# MC21R01_Inverter_1.net
KiCad netlist of a schematic drawn in Altium Designer
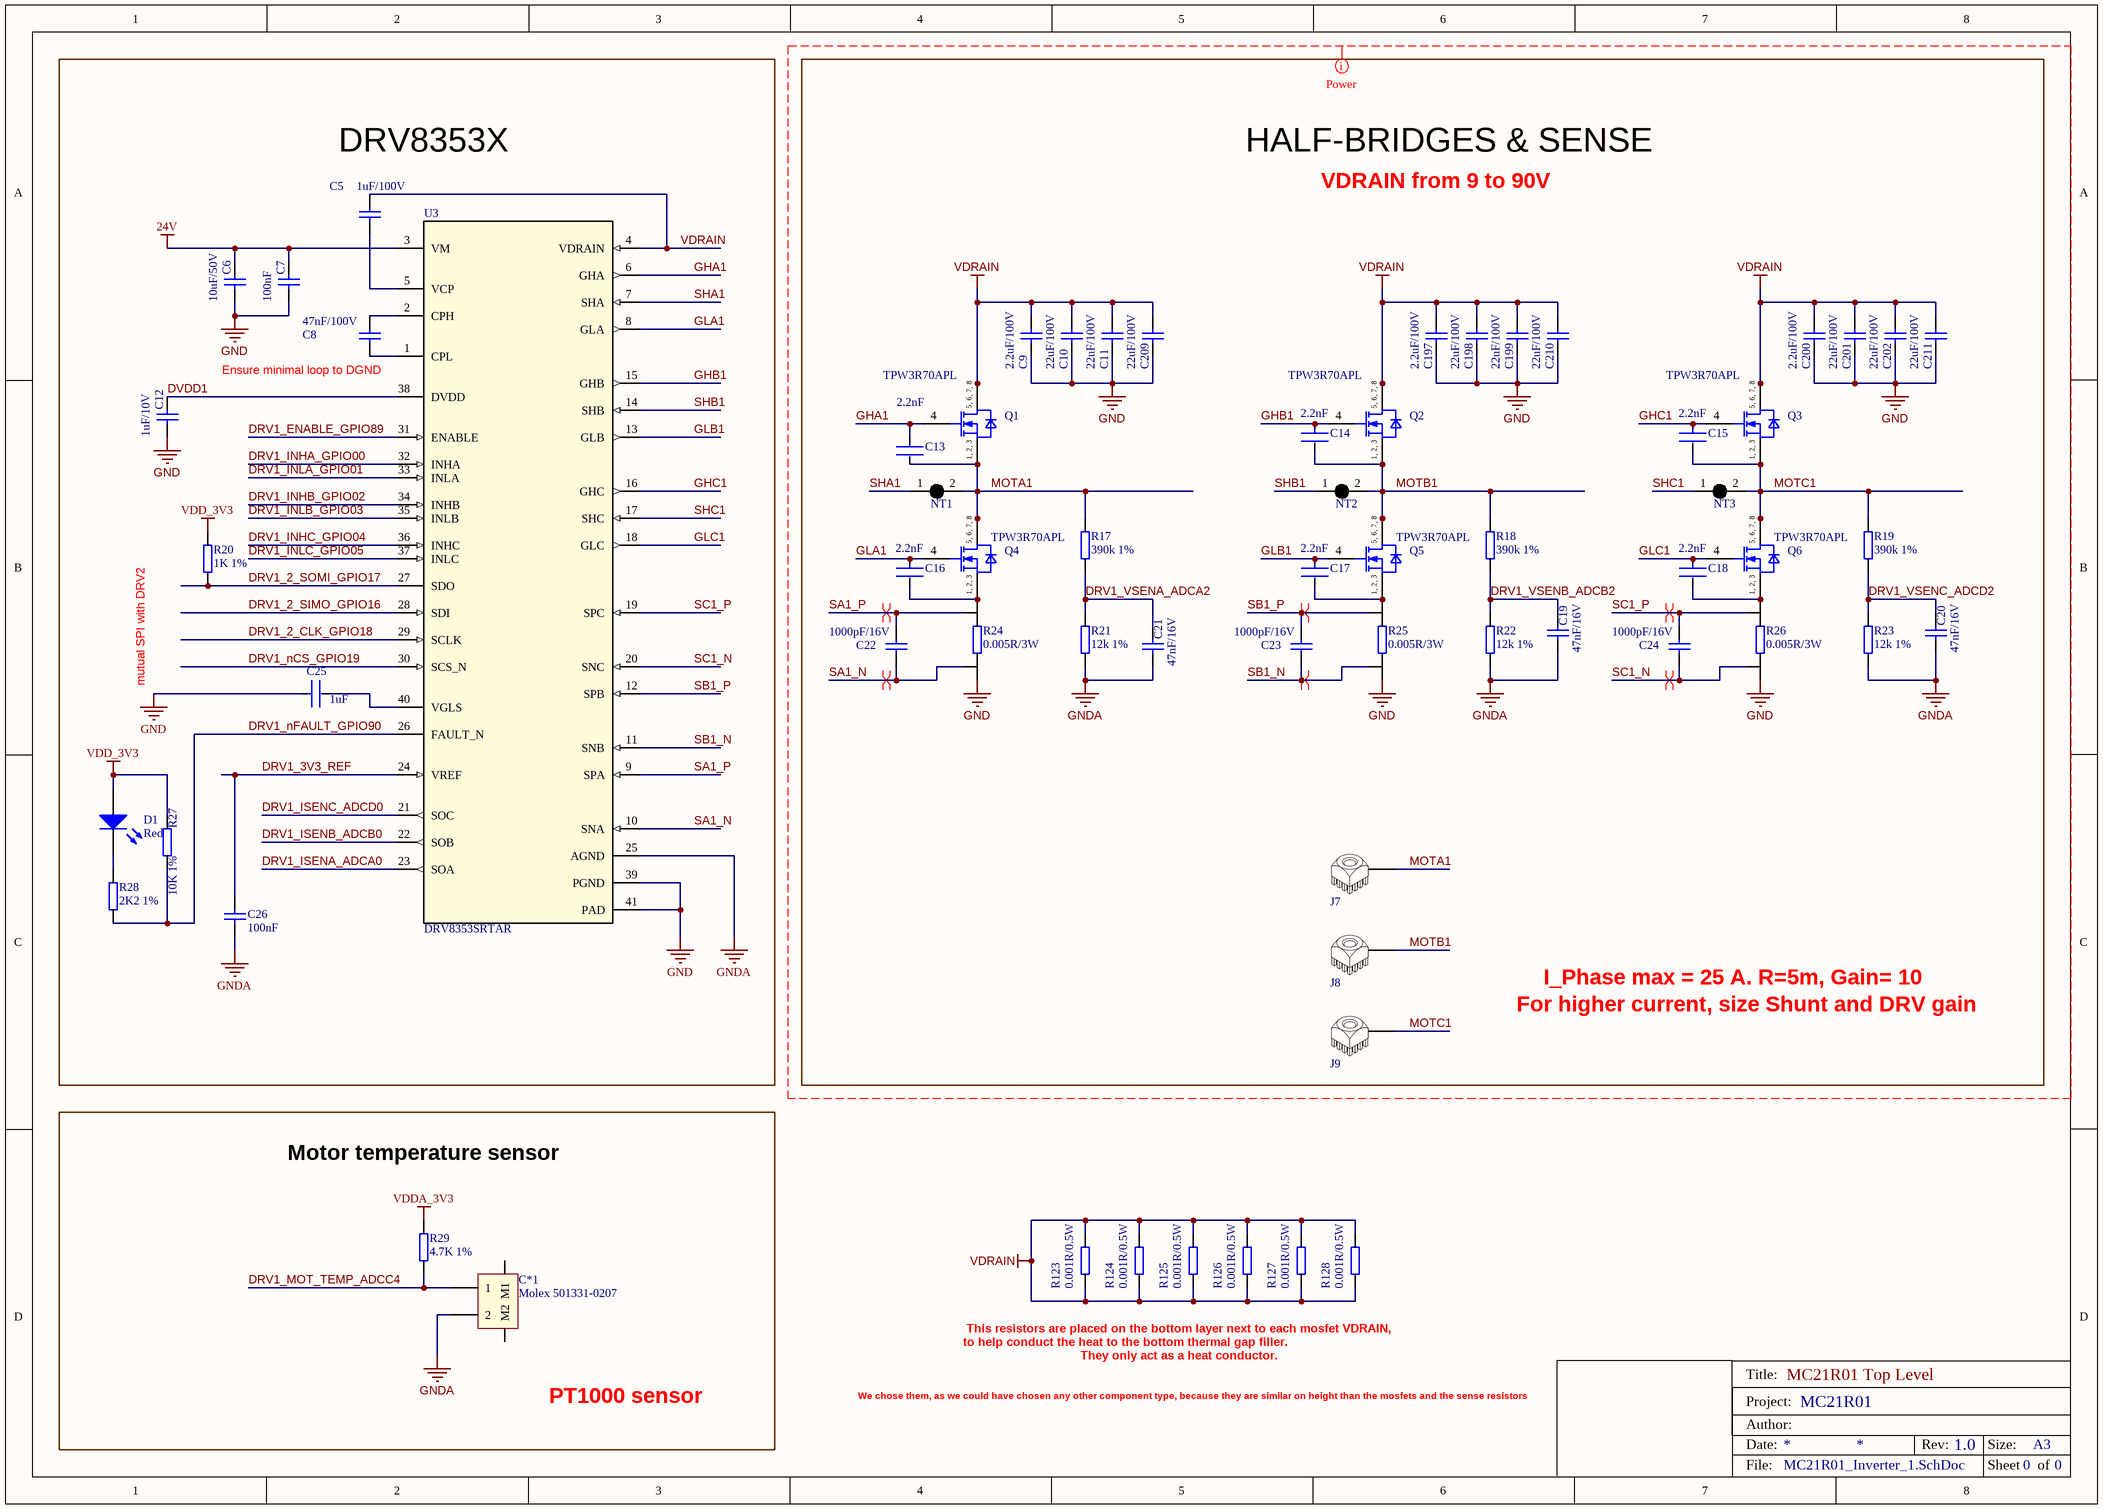
[diagram p0: MC21R01_Inverter_1.SchDoc]

(export (version "E")
  (design (tool "Eeschema 10.0.6"))
  (components
    (comp (ref "C*1")
      (value "Molex 501331-0207")
      (footprint "Molex 501331-0207")
      (description "PicoClasp 02 pin vertical")
      (libsource (lib "PAL_Molex") (part "Molex 501331-0207"))
    )
    (comp (ref "C5")
      (value "1uF/100V")
      (footprint "PAL_Capacitors:0805 SMD capacitor")
      (description "1 uF 100 V 0805  ±10% Tolerance X7R Multilayer Ceramic Chip Capacitor")
      (fields (field (name "Comment") "1uF/100V 0805 10% X7R"))
      (libsource (lib "PAL_Capacitors") (part "1uF/100V 0805 10% X7R"))
    )
    (comp (ref "C6")
      (value "10uF/50V")
      (footprint "PAL_Capacitors:1206 SMD Capacitor")
      (description "10 uF 50 V 1206 ±20% Tolerance X5R Multilayer Ceramic Chip Capacitor")
      (fields (field (name "Comment") "10uf/50V 1206 20% X5R"))
      (libsource (lib "PAL_Capacitors") (part "10uF/50V 1206 20% X5R"))
    )
    (comp (ref "C7")
      (value "100nF")
      (footprint "CAPC0603X03N")
      (description "100nF/25V 0201 10% Tolerance X6S Multilayer Ceramic Chip Capacitor")
      (fields (field (name "TOLERANCE") "10%") (field (name "Comment") "100nF/25V 0201 10% X6S"))
      (libsource (lib "Wandercraft") (part "STD_CAP_2PIN_NPOL"))
    )
    (comp (ref "C8")
      (value "47nF/100V")
      (footprint "PAL_Capacitors:0603 SMD capacitor")
      (description "47 nF 100 V 0603 ±10% Tolerance X7R Multilayer Ceramic Chip Capacitor")
      (fields (field (name "Comment") "47nF/100V 0603 10% X7R"))
      (libsource (lib "PAL_Capacitors") (part "47nF/100V 0603 10% X7R_1"))
    )
    (comp (ref "C9")
      (value "2.2uF/100V")
      (footprint "1210 SMD capacitor h=2mm")
      (description "2.2 uF 100 V 1210  ±10% Tolerance X7R Multilayer Ceramic Chip Capacitor")
      (fields (field (name "Comment") "2.2uF/100V 1210 10% X7R"))
      (libsource (lib "PAL_Capacitors") (part "2.2uF/100V 1210 10% X7R"))
    )
    (comp (ref "C10")
      (value "22uF/100V")
      (footprint "PAL_Capacitors:2220 SMD Capacitor H=5MM")
      (description "22 uF 100 V 2220 ±20% Tolerance X7S Multilayer Ceramic Chip Capacitor")
      (fields (field (name "Comment") "22uF/100V 2220 20% X7S"))
      (libsource (lib "PAL_Capacitors") (part "22uF/100V 2220 20% X7S"))
    )
    (comp (ref "C11")
      (value "22uF/100V")
      (footprint "PAL_Capacitors:2220 SMD Capacitor H=5MM")
      (description "22 uF 100 V 2220 ±20% Tolerance X7S Multilayer Ceramic Chip Capacitor")
      (fields (field (name "Comment") "22uF/100V 2220 20% X7S"))
      (libsource (lib "PAL_Capacitors") (part "22uF/100V 2220 20% X7S"))
    )
    (comp (ref "C12")
      (value "1uF/10V")
      (footprint "PAL_Capacitors:0603 SMD capacitor")
      (description "1uF/10V 0603 10% Tolerance X7R Multilayer Ceramic Chip Capacitor")
      (fields (field (name "Comment") "1uF/10V 0603 10% X7R"))
      (libsource (lib "PAL_Capacitors") (part "1uF/10V 0603 10% X7R"))
    )
    (comp (ref "C13")
      (value "2200pF/50V 0201 10% X7R")
      (footprint "FP-GRM033-0_03-IPC_A")
      (description "2200pF/50V 0201 10% Tolerance X7R Multilayer Ceramic Chip Capacitor")
      (fields (field (name "TOLERANCE") "10%") (field (name "CAPACITANCE") "2.2nF"))
      (libsource (lib "Altium Content Vault") (part "b4654b650e69147ec39a6b967a45e02"))
    )
    (comp (ref "C14")
      (value "2200pF/50V 0201 10% X7R")
      (footprint "FP-GRM033-0_03-IPC_A")
      (description "2200pF/50V 0201 10% Tolerance X7R Multilayer Ceramic Chip Capacitor")
      (fields (field (name "TOLERANCE") "10%") (field (name "CAPACITANCE") "2.2nF"))
      (libsource (lib "Altium Content Vault") (part "b4654b650e69147ec39a6b967a45e02"))
    )
    (comp (ref "C15")
      (value "2200pF/50V 0201 10% X7R")
      (footprint "FP-GRM033-0_03-IPC_A")
      (description "2200pF/50V 0201 10% Tolerance X7R Multilayer Ceramic Chip Capacitor")
      (fields (field (name "TOLERANCE") "10%") (field (name "CAPACITANCE") "2.2nF"))
      (libsource (lib "Altium Content Vault") (part "b4654b650e69147ec39a6b967a45e02"))
    )
    (comp (ref "C16")
      (value "2200pF/50V 0201 10% X7R")
      (footprint "FP-GRM033-0_03-IPC_A")
      (description "2200pF/50V 0201 10% Tolerance X7R Multilayer Ceramic Chip Capacitor")
      (fields (field (name "TOLERANCE") "10%") (field (name "CAPACITANCE") "2.2nF"))
      (libsource (lib "Altium Content Vault") (part "b4654b650e69147ec39a6b967a45e02"))
    )
    (comp (ref "C17")
      (value "2200pF/50V 0201 10% X7R")
      (footprint "FP-GRM033-0_03-IPC_A")
      (description "2200pF/50V 0201 10% Tolerance X7R Multilayer Ceramic Chip Capacitor")
      (fields (field (name "TOLERANCE") "10%") (field (name "CAPACITANCE") "2.2nF"))
      (libsource (lib "Altium Content Vault") (part "b4654b650e69147ec39a6b967a45e02"))
    )
    (comp (ref "C18")
      (value "2200pF/50V 0201 10% X7R")
      (footprint "FP-GRM033-0_03-IPC_A")
      (description "2200pF/50V 0201 10% Tolerance X7R Multilayer Ceramic Chip Capacitor")
      (fields (field (name "TOLERANCE") "10%") (field (name "CAPACITANCE") "2.2nF"))
      (libsource (lib "Altium Content Vault") (part "b4654b650e69147ec39a6b967a45e02"))
    )
    (comp (ref "C19")
      (value "47nF/16V")
      (footprint "PAL_Capacitors:0402 SMD Capacitor")
      (description "47nF/16V 0402 10% Tolerance X7R Multilayer Ceramic Chip Capacitor")
      (fields (field (name "Comment") "47nF/16V 0402 10% X7R"))
      (libsource (lib "PAL_Capacitors") (part "47nF/16V 0402 10% X7R"))
    )
    (comp (ref "C20")
      (value "47nF/16V")
      (footprint "PAL_Capacitors:0402 SMD Capacitor")
      (description "47nF/16V 0402 10% Tolerance X7R Multilayer Ceramic Chip Capacitor")
      (fields (field (name "Comment") "47nF/16V 0402 10% X7R"))
      (libsource (lib "PAL_Capacitors") (part "47nF/16V 0402 10% X7R"))
    )
    (comp (ref "C21")
      (value "47nF/16V")
      (footprint "PAL_Capacitors:0402 SMD Capacitor")
      (description "47nF/16V 0402 10% Tolerance X7R Multilayer Ceramic Chip Capacitor")
      (fields (field (name "Comment") "47nF/16V 0402 10% X7R"))
      (libsource (lib "PAL_Capacitors") (part "47nF/16V 0402 10% X7R"))
    )
    (comp (ref "C22")
      (value "1000pF/16V")
      (footprint "PAL_Capacitors:0402 SMD Capacitor")
      (description "1000pF/16V 0402 10% Tolerance X7R Multilayer Ceramic Chip Capacitor")
      (fields (field (name "Comment") "1000pF/16V 0402 10% X7R"))
      (libsource (lib "PAL_Capacitors") (part "1000pF/16V 0402 10% X7R_1"))
    )
    (comp (ref "C23")
      (value "1000pF/16V")
      (footprint "PAL_Capacitors:0402 SMD Capacitor")
      (description "1000pF/16V 0402 10% Tolerance X7R Multilayer Ceramic Chip Capacitor")
      (fields (field (name "Comment") "1000pF/16V 0402 10% X7R"))
      (libsource (lib "PAL_Capacitors") (part "1000pF/16V 0402 10% X7R_1"))
    )
    (comp (ref "C24")
      (value "1000pF/16V")
      (footprint "PAL_Capacitors:0402 SMD Capacitor")
      (description "1000pF/16V 0402 10% Tolerance X7R Multilayer Ceramic Chip Capacitor")
      (fields (field (name "Comment") "1000pF/16V 0402 10% X7R"))
      (libsource (lib "PAL_Capacitors") (part "1000pF/16V 0402 10% X7R_1"))
    )
    (comp (ref "C25")
      (value "1uF/6.3V 0201 10% X5R")
      (footprint "FP-CL03-IPC_A")
      (description "1uF/6.3V 0201 10% Tolerance X5R Multilayer Ceramic Chip Capacitor")
      (fields (field (name "TOLERANCE") "20%") (field (name "CAPACITANCE") "1uF"))
      (libsource (lib "Altium Content Vault") (part "b4654b650e69147ec39a6b967a45e02"))
    )
    (comp (ref "C26")
      (value "100nF")
      (footprint "CAPC0603X03N")
      (description "100nF/25V 0201 10% Tolerance X6S Multilayer Ceramic Chip Capacitor")
      (fields (field (name "TOLERANCE") "10%") (field (name "Comment") "100nF/25V 0201 10% X6S"))
      (libsource (lib "Wandercraft") (part "STD_CAP_2PIN_NPOL"))
    )
    (comp (ref "C197")
      (value "2.2uF/100V")
      (footprint "1210 SMD capacitor h=2mm")
      (description "2.2 uF 100 V 1210  ±10% Tolerance X7R Multilayer Ceramic Chip Capacitor")
      (fields (field (name "Comment") "2.2uF/100V 1210 10% X7R"))
      (libsource (lib "PAL_Capacitors") (part "2.2uF/100V 1210 10% X7R"))
    )
    (comp (ref "C198")
      (value "22uF/100V")
      (footprint "PAL_Capacitors:2220 SMD Capacitor H=5MM")
      (description "22 uF 100 V 2220 ±20% Tolerance X7S Multilayer Ceramic Chip Capacitor")
      (fields (field (name "Comment") "22uF/100V 2220 20% X7S"))
      (libsource (lib "PAL_Capacitors") (part "22uF/100V 2220 20% X7S"))
    )
    (comp (ref "C199")
      (value "22uF/100V")
      (footprint "PAL_Capacitors:2220 SMD Capacitor H=5MM")
      (description "22 uF 100 V 2220 ±20% Tolerance X7S Multilayer Ceramic Chip Capacitor")
      (fields (field (name "Comment") "22uF/100V 2220 20% X7S"))
      (libsource (lib "PAL_Capacitors") (part "22uF/100V 2220 20% X7S"))
    )
    (comp (ref "C200")
      (value "2.2uF/100V")
      (footprint "1210 SMD capacitor h=2mm")
      (description "2.2 uF 100 V 1210  ±10% Tolerance X7R Multilayer Ceramic Chip Capacitor")
      (fields (field (name "Comment") "2.2uF/100V 1210 10% X7R"))
      (libsource (lib "PAL_Capacitors") (part "2.2uF/100V 1210 10% X7R"))
    )
    (comp (ref "C201")
      (value "22uF/100V")
      (footprint "PAL_Capacitors:2220 SMD Capacitor H=5MM")
      (description "22 uF 100 V 2220 ±20% Tolerance X7S Multilayer Ceramic Chip Capacitor")
      (fields (field (name "Comment") "22uF/100V 2220 20% X7S"))
      (libsource (lib "PAL_Capacitors") (part "22uF/100V 2220 20% X7S"))
    )
    (comp (ref "C202")
      (value "22uF/100V")
      (footprint "PAL_Capacitors:2220 SMD Capacitor H=5MM")
      (description "22 uF 100 V 2220 ±20% Tolerance X7S Multilayer Ceramic Chip Capacitor")
      (fields (field (name "Comment") "22uF/100V 2220 20% X7S"))
      (libsource (lib "PAL_Capacitors") (part "22uF/100V 2220 20% X7S"))
    )
    (comp (ref "C209")
      (value "22uF/100V")
      (footprint "PAL_Capacitors:2220 SMD Capacitor H=5MM")
      (description "22 uF 100 V 2220 ±20% Tolerance X7S Multilayer Ceramic Chip Capacitor")
      (fields (field (name "Comment") "22uF/100V 2220 20% X7S"))
      (libsource (lib "PAL_Capacitors") (part "22uF/100V 2220 20% X7S"))
    )
    (comp (ref "C210")
      (value "22uF/100V")
      (footprint "PAL_Capacitors:2220 SMD Capacitor H=5MM")
      (description "22 uF 100 V 2220 ±20% Tolerance X7S Multilayer Ceramic Chip Capacitor")
      (fields (field (name "Comment") "22uF/100V 2220 20% X7S"))
      (libsource (lib "PAL_Capacitors") (part "22uF/100V 2220 20% X7S"))
    )
    (comp (ref "C211")
      (value "22uF/100V")
      (footprint "PAL_Capacitors:2220 SMD Capacitor H=5MM")
      (description "22 uF 100 V 2220 ±20% Tolerance X7S Multilayer Ceramic Chip Capacitor")
      (fields (field (name "Comment") "22uF/100V 2220 20% X7S"))
      (libsource (lib "PAL_Capacitors") (part "22uF/100V 2220 20% X7S"))
    )
    (comp (ref "D1")
      (value "Red")
      (footprint "0402 SMD LED Red")
      (description "Low Profile Chip LED, Red")
      (fields (field (name "MANUFACTURER") "ROHM") (field (name "MANUFACTURER PART NUMBER") "SML-P11UTT86R"))
      (libsource (lib "PAL_devices") (part "LED_0402_Red"))
    )
    (comp (ref "J7")
      (value "WE_7461094")
      (footprint "WE_7461094")
      (description "REDCUBE PRESS-FIT with external thread and full plain pin-plate WPSHFU, 130A, M3 screw, 9pins")
      (fields
        (field (name "MANUFACTURER") "WURTH ELEKTRONIK")
        (field (name "MANUFACTURER PART NUMBER") "7461094")
        (field (name "CREATED BY") "Yaiza Montes")
      )
      (libsource (lib "PAL_Wurth_2020") (part "WE_7461094"))
    )
    (comp (ref "J8")
      (value "WE_7461094")
      (footprint "WE_7461094")
      (description "REDCUBE PRESS-FIT with external thread and full plain pin-plate WPSHFU, 130A, M3 screw, 9pins")
      (fields
        (field (name "MANUFACTURER") "WURTH ELEKTRONIK")
        (field (name "MANUFACTURER PART NUMBER") "7461094")
        (field (name "CREATED BY") "Yaiza Montes")
      )
      (libsource (lib "PAL_Wurth_2020") (part "WE_7461094"))
    )
    (comp (ref "J9")
      (value "WE_7461094")
      (footprint "WE_7461094")
      (description "REDCUBE PRESS-FIT with external thread and full plain pin-plate WPSHFU, 130A, M3 screw, 9pins")
      (fields
        (field (name "MANUFACTURER") "WURTH ELEKTRONIK")
        (field (name "MANUFACTURER PART NUMBER") "7461094")
        (field (name "CREATED BY") "Yaiza Montes")
      )
      (libsource (lib "PAL_Wurth_2020") (part "WE_7461094"))
    )
    (comp (ref "NT1")
      (value "Net Tie SMD")
      (footprint "PAL_devices:Net Tie SMD 0.4x0.8mm")
      (description "Net Tie starpoint")
      (libsource (lib "PAL_devices") (part "Net Tie SMD"))
    )
    (comp (ref "NT2")
      (value "Net Tie SMD")
      (footprint "PAL_devices:Net Tie SMD 0.4x0.8mm")
      (description "Net Tie starpoint")
      (libsource (lib "PAL_devices") (part "Net Tie SMD"))
    )
    (comp (ref "NT3")
      (value "Net Tie SMD")
      (footprint "PAL_devices:Net Tie SMD 0.4x0.8mm")
      (description "Net Tie starpoint")
      (libsource (lib "PAL_devices") (part "Net Tie SMD"))
    )
    (comp (ref "Q1")
      (value "TPW3R70APL")
      (footprint "DSOP Advance Toshiba")
      (description "Silicon N-channel MOS (U-MOS-H)")
      (fields (field (name "MANUFACTURER") "Toshiba Semicon"))
      (libsource (lib "PAL_devices") (part "TPW3R70APL"))
    )
    (comp (ref "Q2")
      (value "TPW3R70APL")
      (footprint "DSOP Advance Toshiba")
      (description "Silicon N-channel MOS (U-MOS-H)")
      (fields (field (name "MANUFACTURER") "Toshiba Semicon"))
      (libsource (lib "PAL_devices") (part "TPW3R70APL"))
    )
    (comp (ref "Q3")
      (value "TPW3R70APL")
      (footprint "DSOP Advance Toshiba")
      (description "Silicon N-channel MOS (U-MOS-H)")
      (fields (field (name "MANUFACTURER") "Toshiba Semicon"))
      (libsource (lib "PAL_devices") (part "TPW3R70APL"))
    )
    (comp (ref "Q4")
      (value "TPW3R70APL")
      (footprint "DSOP Advance Toshiba")
      (description "Silicon N-channel MOS (U-MOS-H)")
      (fields (field (name "MANUFACTURER") "Toshiba Semicon"))
      (libsource (lib "PAL_devices") (part "TPW3R70APL"))
    )
    (comp (ref "Q5")
      (value "TPW3R70APL")
      (footprint "DSOP Advance Toshiba")
      (description "Silicon N-channel MOS (U-MOS-H)")
      (fields (field (name "MANUFACTURER") "Toshiba Semicon"))
      (libsource (lib "PAL_devices") (part "TPW3R70APL"))
    )
    (comp (ref "Q6")
      (value "TPW3R70APL")
      (footprint "DSOP Advance Toshiba")
      (description "Silicon N-channel MOS (U-MOS-H)")
      (fields (field (name "MANUFACTURER") "Toshiba Semicon"))
      (libsource (lib "PAL_devices") (part "TPW3R70APL"))
    )
    (comp (ref "R17")
      (value "390k 1%")
      (footprint "PAL_Resistors:0603 SMD resistor")
      (description "390k/150V 1% 0603 250mW SMD Resistor")
      (libsource (lib "PAL_Resistors") (part "390k/150V 1% 0603 250mW"))
    )
    (comp (ref "R18")
      (value "390k 1%")
      (footprint "PAL_Resistors:0603 SMD resistor")
      (description "390k/150V 1% 0603 250mW SMD Resistor")
      (libsource (lib "PAL_Resistors") (part "390k/150V 1% 0603 250mW"))
    )
    (comp (ref "R19")
      (value "390k 1%")
      (footprint "PAL_Resistors:0603 SMD resistor")
      (description "390k/150V 1% 0603 250mW SMD Resistor")
      (libsource (lib "PAL_Resistors") (part "390k/150V 1% 0603 250mW"))
    )
    (comp (ref "R20")
      (value "1K 1%")
      (footprint "0402 SMD rESISTOR")
      (description "1K/50V 1% 0402 100mW SMD Resistor")
      (libsource (lib "PAL_Resistors") (part "1K/50V 1% 0402 100mW"))
    )
    (comp (ref "R21")
      (value "12k 1%")
      (footprint "PAL_Resistors:0603 SMD resistor")
      (description "12k/150V 1% 0603 250mW SMD Resistor")
      (libsource (lib "PAL_Resistors") (part "12k/150V 1% 0603 250mW"))
    )
    (comp (ref "R22")
      (value "12k 1%")
      (footprint "PAL_Resistors:0603 SMD resistor")
      (description "12k/150V 1% 0603 250mW SMD Resistor")
      (libsource (lib "PAL_Resistors") (part "12k/150V 1% 0603 250mW"))
    )
    (comp (ref "R23")
      (value "12k 1%")
      (footprint "PAL_Resistors:0603 SMD resistor")
      (description "12k/150V 1% 0603 250mW SMD Resistor")
      (libsource (lib "PAL_Resistors") (part "12k/150V 1% 0603 250mW"))
    )
    (comp (ref "R24")
      (value "0.005R/3W")
      (footprint "PAL_Resistors:2512 SMD Resistor V2 NETTIE")
      (description "0.005R/3W 1% 2512 shunt SMD Resistor")
      (libsource (lib "PAL_Resistors") (part "0.005R/3W 1% 2512 Shunt"))
    )
    (comp (ref "R25")
      (value "0.005R/3W")
      (footprint "PAL_Resistors:2512 SMD Resistor V2 NETTIE")
      (description "0.005R/3W 1% 2512 shunt SMD Resistor")
      (libsource (lib "PAL_Resistors") (part "0.005R/3W 1% 2512 Shunt"))
    )
    (comp (ref "R26")
      (value "0.005R/3W")
      (footprint "PAL_Resistors:2512 SMD Resistor V2 NETTIE")
      (description "0.005R/3W 1% 2512 shunt SMD Resistor")
      (libsource (lib "PAL_Resistors") (part "0.005R/3W 1% 2512 Shunt"))
    )
    (comp (ref "R27")
      (value "10K 1%")
      (footprint "0402 SMD rESISTOR")
      (description "10K/50V 1% 0402 100mW SMD Resistor")
      (libsource (lib "PAL_Resistors") (part "10K/50V 1% 0402 100mW"))
    )
    (comp (ref "R28")
      (value "2K2 1%")
      (footprint "0402 SMD rESISTOR")
      (description "2K2/50V 1% 0402 100mW SMD Resistor")
      (libsource (lib "PAL_Resistors") (part "2K2/50V 1% 0402 100mW"))
    )
    (comp (ref "R29")
      (value "4.7K 1%")
      (footprint "0402 SMD rESISTOR")
      (description "4.7K/50V 1% 0402 100mW SMD Resistor")
      (libsource (lib "PAL_Resistors") (part "4.7K/50V 1% 0402 100mW"))
    )
    (comp (ref "R123")
      (value "0.001R/0.5W")
      (footprint "PAL_Resistors:2010 SMD Resistor VERTICAL")
      (description "0.001R/0.5W 1% 2010 shunt SMD Resistor")
      (libsource (lib "PAL_Resistors") (part "0.001R/0.5W 1% 2010 Shunt"))
    )
    (comp (ref "R124")
      (value "0.001R/0.5W")
      (footprint "PAL_Resistors:2010 SMD Resistor VERTICAL")
      (description "0.001R/0.5W 1% 2010 shunt SMD Resistor")
      (libsource (lib "PAL_Resistors") (part "0.001R/0.5W 1% 2010 Shunt"))
    )
    (comp (ref "R125")
      (value "0.001R/0.5W")
      (footprint "PAL_Resistors:2010 SMD Resistor VERTICAL")
      (description "0.001R/0.5W 1% 2010 shunt SMD Resistor")
      (libsource (lib "PAL_Resistors") (part "0.001R/0.5W 1% 2010 Shunt"))
    )
    (comp (ref "R126")
      (value "0.001R/0.5W")
      (footprint "PAL_Resistors:2010 SMD Resistor VERTICAL")
      (description "0.001R/0.5W 1% 2010 shunt SMD Resistor")
      (libsource (lib "PAL_Resistors") (part "0.001R/0.5W 1% 2010 Shunt"))
    )
    (comp (ref "R127")
      (value "0.001R/0.5W")
      (footprint "PAL_Resistors:2010 SMD Resistor VERTICAL")
      (description "0.001R/0.5W 1% 2010 shunt SMD Resistor")
      (libsource (lib "PAL_Resistors") (part "0.001R/0.5W 1% 2010 Shunt"))
    )
    (comp (ref "R128")
      (value "0.001R/0.5W")
      (footprint "PAL_Resistors:2010 SMD Resistor VERTICAL")
      (description "0.001R/0.5W 1% 2010 shunt SMD Resistor")
      (libsource (lib "PAL_Resistors") (part "0.001R/0.5W 1% 2010 Shunt"))
    )
    (comp (ref "U3")
      (value "DRV8353SRTAR")
      (footprint "PAL_IPC-7351B_Footprints:QFN50P600X600X80_HS-41N")
      (description "102-V max 3-phase smart gate driver with current shunt amplifiers")
      (fields (field (name "MANUFACTURER") "Texas Instruments"))
      (libsource (lib "PAL_devices") (part "DRV8353SRTAR"))
    )
  )
  (nets
    (net (code "1") (name "/DRV1_2_CLK_GPIO18") (class "Default")
      (node (ref "U3") (pin "29") (pinfunction "SCLK_29") (pintype "input"))
    )
    (net (code "2") (name "/DRV1_2_SIMO_GPIO16") (class "Default")
      (node (ref "U3") (pin "28") (pinfunction "SDI_28") (pintype "input"))
    )
    (net (code "3") (name "/DRV1_2_SOMI_GPIO17") (class "Default")
      (node (ref "R20") (pin "1") (pinfunction "1_1") (pintype "passive"))
      (node (ref "U3") (pin "27") (pinfunction "SDO_27") (pintype "passive"))
    )
    (net (code "4") (name "/DRV1_3V3_REF") (class "Default")
      (node (ref "C26") (pin "2") (pinfunction "2_2") (pintype "passive"))
      (node (ref "U3") (pin "24") (pinfunction "VREF_24") (pintype "input"))
    )
    (net (code "5") (name "/DRV1_ENABLE_GPIO89") (class "Default")
      (node (ref "U3") (pin "31") (pinfunction "ENABLE_31") (pintype "input"))
    )
    (net (code "6") (name "/DRV1_INHA_GPIO00") (class "Default")
      (node (ref "U3") (pin "32") (pinfunction "INHA_32") (pintype "input"))
    )
    (net (code "7") (name "/DRV1_INHB_GPIO02") (class "Default")
      (node (ref "U3") (pin "34") (pinfunction "INHB_34") (pintype "input"))
    )
    (net (code "8") (name "/DRV1_INHC_GPIO04") (class "Default")
      (node (ref "U3") (pin "36") (pinfunction "INHC_36") (pintype "input"))
    )
    (net (code "9") (name "/DRV1_INLA_GPIO01") (class "Default")
      (node (ref "U3") (pin "33") (pinfunction "INLA_33") (pintype "input"))
    )
    (net (code "10") (name "/DRV1_INLB_GPIO03") (class "Default")
      (node (ref "U3") (pin "35") (pinfunction "INLB_35") (pintype "input"))
    )
    (net (code "11") (name "/DRV1_INLC_GPIO05") (class "Default")
      (node (ref "U3") (pin "37") (pinfunction "INLC_37") (pintype "input"))
    )
    (net (code "12") (name "/DRV1_ISENA_ADCA0") (class "Default")
      (node (ref "U3") (pin "23") (pinfunction "SOA_23") (pintype "output"))
    )
    (net (code "13") (name "/DRV1_ISENB_ADCB0") (class "Default")
      (node (ref "U3") (pin "22") (pinfunction "SOB_22") (pintype "output"))
    )
    (net (code "14") (name "/DRV1_ISENC_ADCD0") (class "Default")
      (node (ref "U3") (pin "21") (pinfunction "SOC_21") (pintype "output"))
    )
    (net (code "15") (name "/DRV1_MOT_TEMP_ADCC4") (class "Default")
      (node (ref "C*1") (pin "1") (pinfunction "1_1") (pintype "passive"))
      (node (ref "R29") (pin "1") (pinfunction "1_1") (pintype "passive"))
    )
    (net (code "16") (name "/DRV1_VSENA_ADCA2") (class "Default")
      (node (ref "C21") (pin "1") (pinfunction "1_1") (pintype "passive"))
      (node (ref "R17") (pin "1") (pinfunction "1_1") (pintype "passive"))
      (node (ref "R21") (pin "2") (pinfunction "2_2") (pintype "passive"))
    )
    (net (code "17") (name "/DRV1_VSENB_ADCB2") (class "Default")
      (node (ref "C19") (pin "1") (pinfunction "1_1") (pintype "passive"))
      (node (ref "R18") (pin "1") (pinfunction "1_1") (pintype "passive"))
      (node (ref "R22") (pin "2") (pinfunction "2_2") (pintype "passive"))
    )
    (net (code "18") (name "/DRV1_VSENC_ADCD2") (class "Default")
      (node (ref "C20") (pin "1") (pinfunction "1_1") (pintype "passive"))
      (node (ref "R19") (pin "1") (pinfunction "1_1") (pintype "passive"))
      (node (ref "R23") (pin "2") (pinfunction "2_2") (pintype "passive"))
    )
    (net (code "19") (name "/DRV1_nCS_GPIO19") (class "Default")
      (node (ref "U3") (pin "30") (pinfunction "SCS_N_30") (pintype "input"))
    )
    (net (code "20") (name "/DRV1_nFAULT_GPIO90") (class "Default")
      (node (ref "R27") (pin "1") (pinfunction "1_1") (pintype "passive"))
      (node (ref "R28") (pin "1") (pinfunction "1_1") (pintype "passive"))
      (node (ref "U3") (pin "26") (pinfunction "FAULT_N_26") (pintype "open_collector"))
    )
    (net (code "21") (name "/DVDD1") (class "Default")
      (node (ref "C12") (pin "1") (pinfunction "1_1") (pintype "passive"))
      (node (ref "U3") (pin "38") (pinfunction "DVDD_38") (pintype "power_in"))
    )
    (net (code "22") (name "/GHA1") (class "Default")
      (node (ref "C13") (pin "1") (pinfunction "1_1") (pintype "passive"))
      (node (ref "Q1") (pin "4") (pinfunction "GATE_4") (pintype "passive"))
      (node (ref "U3") (pin "6") (pinfunction "GHA_6") (pintype "output"))
    )
    (net (code "23") (name "/GHB1") (class "Default")
      (node (ref "C14") (pin "1") (pinfunction "1_1") (pintype "passive"))
      (node (ref "Q2") (pin "4") (pinfunction "GATE_4") (pintype "passive"))
      (node (ref "U3") (pin "15") (pinfunction "GHB_15") (pintype "output"))
    )
    (net (code "24") (name "/GHC1") (class "Default")
      (node (ref "C15") (pin "1") (pinfunction "1_1") (pintype "passive"))
      (node (ref "Q3") (pin "4") (pinfunction "GATE_4") (pintype "passive"))
      (node (ref "U3") (pin "16") (pinfunction "GHC_16") (pintype "output"))
    )
    (net (code "25") (name "/GLA1") (class "Default")
      (node (ref "C16") (pin "1") (pinfunction "1_1") (pintype "passive"))
      (node (ref "Q4") (pin "4") (pinfunction "GATE_4") (pintype "passive"))
      (node (ref "U3") (pin "8") (pinfunction "GLA_8") (pintype "output"))
    )
    (net (code "26") (name "/GLB1") (class "Default")
      (node (ref "C17") (pin "1") (pinfunction "1_1") (pintype "passive"))
      (node (ref "Q5") (pin "4") (pinfunction "GATE_4") (pintype "passive"))
      (node (ref "U3") (pin "13") (pinfunction "GLB_13") (pintype "output"))
    )
    (net (code "27") (name "/GLC1") (class "Default")
      (node (ref "C18") (pin "1") (pinfunction "1_1") (pintype "passive"))
      (node (ref "Q6") (pin "4") (pinfunction "GATE_4") (pintype "passive"))
      (node (ref "U3") (pin "18") (pinfunction "GLC_18") (pintype "output"))
    )
    (net (code "28") (name "/MOTA1") (class "Default")
      (node (ref "C13") (pin "2") (pinfunction "2_2") (pintype "passive"))
      (node (ref "J7") (pin "1") (pinfunction "1_1") (pintype "passive"))
      (node (ref "NT1") (pin "2") (pinfunction "2_2") (pintype "passive"))
      (node (ref "Q1") (pin "1") (pinfunction "SOURCE_1") (pintype "passive"))
      (node (ref "Q1") (pin "2") (pinfunction "SOURCE_2") (pintype "passive"))
      (node (ref "Q1") (pin "3") (pinfunction "SOURCE_3") (pintype "passive"))
      (node (ref "Q4") (pin "5") (pinfunction "DRAIN_5") (pintype "passive"))
      (node (ref "Q4") (pin "6") (pinfunction "DRAIN_6") (pintype "passive"))
      (node (ref "Q4") (pin "7") (pinfunction "DRAIN_7") (pintype "passive"))
      (node (ref "Q4") (pin "8") (pinfunction "DRAIN_8") (pintype "passive"))
      (node (ref "R17") (pin "2") (pinfunction "2_2") (pintype "passive"))
    )
    (net (code "29") (name "/MOTB1") (class "Default")
      (node (ref "C14") (pin "2") (pinfunction "2_2") (pintype "passive"))
      (node (ref "J8") (pin "1") (pinfunction "1_1") (pintype "passive"))
      (node (ref "NT2") (pin "2") (pinfunction "2_2") (pintype "passive"))
      (node (ref "Q2") (pin "1") (pinfunction "SOURCE_1") (pintype "passive"))
      (node (ref "Q2") (pin "2") (pinfunction "SOURCE_2") (pintype "passive"))
      (node (ref "Q2") (pin "3") (pinfunction "SOURCE_3") (pintype "passive"))
      (node (ref "Q5") (pin "5") (pinfunction "DRAIN_5") (pintype "passive"))
      (node (ref "Q5") (pin "6") (pinfunction "DRAIN_6") (pintype "passive"))
      (node (ref "Q5") (pin "7") (pinfunction "DRAIN_7") (pintype "passive"))
      (node (ref "Q5") (pin "8") (pinfunction "DRAIN_8") (pintype "passive"))
      (node (ref "R18") (pin "2") (pinfunction "2_2") (pintype "passive"))
    )
    (net (code "30") (name "/MOTC1") (class "Default")
      (node (ref "C15") (pin "2") (pinfunction "2_2") (pintype "passive"))
      (node (ref "J9") (pin "1") (pinfunction "1_1") (pintype "passive"))
      (node (ref "NT3") (pin "2") (pinfunction "2_2") (pintype "passive"))
      (node (ref "Q3") (pin "1") (pinfunction "SOURCE_1") (pintype "passive"))
      (node (ref "Q3") (pin "2") (pinfunction "SOURCE_2") (pintype "passive"))
      (node (ref "Q3") (pin "3") (pinfunction "SOURCE_3") (pintype "passive"))
      (node (ref "Q6") (pin "5") (pinfunction "DRAIN_5") (pintype "passive"))
      (node (ref "Q6") (pin "6") (pinfunction "DRAIN_6") (pintype "passive"))
      (node (ref "Q6") (pin "7") (pinfunction "DRAIN_7") (pintype "passive"))
      (node (ref "Q6") (pin "8") (pinfunction "DRAIN_8") (pintype "passive"))
      (node (ref "R19") (pin "2") (pinfunction "2_2") (pintype "passive"))
    )
    (net (code "31") (name "/SA1_N") (class "Default")
      (node (ref "C22") (pin "2") (pinfunction "2_2") (pintype "passive"))
      (node (ref "R24") (pin "3") (pinfunction "3_3") (pintype "passive"))
      (node (ref "U3") (pin "10") (pinfunction "SNA_10") (pintype "input"))
    )
    (net (code "32") (name "/SA1_P") (class "Default")
      (node (ref "C22") (pin "1") (pinfunction "1_1") (pintype "passive"))
      (node (ref "R24") (pin "4") (pinfunction "4_4") (pintype "passive"))
      (node (ref "U3") (pin "9") (pinfunction "SPA_9") (pintype "input"))
    )
    (net (code "33") (name "/SB1_N") (class "Default")
      (node (ref "C23") (pin "2") (pinfunction "2_2") (pintype "passive"))
      (node (ref "R25") (pin "3") (pinfunction "3_3") (pintype "passive"))
      (node (ref "U3") (pin "11") (pinfunction "SNB_11") (pintype "input"))
    )
    (net (code "34") (name "/SB1_P") (class "Default")
      (node (ref "C23") (pin "1") (pinfunction "1_1") (pintype "passive"))
      (node (ref "R25") (pin "4") (pinfunction "4_4") (pintype "passive"))
      (node (ref "U3") (pin "12") (pinfunction "SPB_12") (pintype "input"))
    )
    (net (code "35") (name "/SC1_N") (class "Default")
      (node (ref "C24") (pin "2") (pinfunction "2_2") (pintype "passive"))
      (node (ref "R26") (pin "3") (pinfunction "3_3") (pintype "passive"))
      (node (ref "U3") (pin "20") (pinfunction "SNC_20") (pintype "input"))
    )
    (net (code "36") (name "/SC1_P") (class "Default")
      (node (ref "C24") (pin "1") (pinfunction "1_1") (pintype "passive"))
      (node (ref "R26") (pin "4") (pinfunction "4_4") (pintype "passive"))
      (node (ref "U3") (pin "19") (pinfunction "SPC_19") (pintype "input"))
    )
    (net (code "37") (name "/SHA1") (class "Default")
      (node (ref "NT1") (pin "1") (pinfunction "1_1") (pintype "passive"))
      (node (ref "U3") (pin "7") (pinfunction "SHA_7") (pintype "input"))
    )
    (net (code "38") (name "/SHB1") (class "Default")
      (node (ref "NT2") (pin "1") (pinfunction "1_1") (pintype "passive"))
      (node (ref "U3") (pin "14") (pinfunction "SHB_14") (pintype "input"))
    )
    (net (code "39") (name "/SHC1") (class "Default")
      (node (ref "NT3") (pin "1") (pinfunction "1_1") (pintype "passive"))
      (node (ref "U3") (pin "17") (pinfunction "SHC_17") (pintype "input"))
    )
    (net (code "40") (name "24V") (class "Default")
      (node (ref "C6") (pin "1") (pinfunction "1_1") (pintype "passive"))
      (node (ref "C7") (pin "2") (pinfunction "2_2") (pintype "passive"))
      (node (ref "U3") (pin "3") (pinfunction "VM_3") (pintype "power_in"))
    )
    (net (code "41") (name "GND") (class "Default")
      (node (ref "C10") (pin "2") (pinfunction "2_2") (pintype "passive"))
      (node (ref "C11") (pin "2") (pinfunction "2_2") (pintype "passive"))
      (node (ref "C12") (pin "2") (pinfunction "2_2") (pintype "passive"))
      (node (ref "C197") (pin "2") (pinfunction "2_2") (pintype "passive"))
      (node (ref "C198") (pin "2") (pinfunction "2_2") (pintype "passive"))
      (node (ref "C199") (pin "2") (pinfunction "2_2") (pintype "passive"))
      (node (ref "C200") (pin "2") (pinfunction "2_2") (pintype "passive"))
      (node (ref "C201") (pin "2") (pinfunction "2_2") (pintype "passive"))
      (node (ref "C202") (pin "2") (pinfunction "2_2") (pintype "passive"))
      (node (ref "C209") (pin "2") (pinfunction "2_2") (pintype "passive"))
      (node (ref "C210") (pin "2") (pinfunction "2_2") (pintype "passive"))
      (node (ref "C211") (pin "2") (pinfunction "2_2") (pintype "passive"))
      (node (ref "C25") (pin "1") (pinfunction "1_1") (pintype "passive"))
      (node (ref "C6") (pin "2") (pinfunction "2_2") (pintype "passive"))
      (node (ref "C7") (pin "1") (pinfunction "1_1") (pintype "passive"))
      (node (ref "C9") (pin "2") (pinfunction "2_2") (pintype "passive"))
      (node (ref "R24") (pin "1") (pinfunction "1_1") (pintype "passive"))
      (node (ref "R25") (pin "1") (pinfunction "1_1") (pintype "passive"))
      (node (ref "R26") (pin "1") (pinfunction "1_1") (pintype "passive"))
      (node (ref "U3") (pin "39") (pinfunction "PGND_39") (pintype "power_in"))
      (node (ref "U3") (pin "41") (pinfunction "PAD_41") (pintype "power_in"))
    )
    (net (code "42") (name "GNDA") (class "Default")
      (node (ref "C*1") (pin "2") (pinfunction "2_2") (pintype "passive"))
      (node (ref "C19") (pin "2") (pinfunction "2_2") (pintype "passive"))
      (node (ref "C20") (pin "2") (pinfunction "2_2") (pintype "passive"))
      (node (ref "C21") (pin "2") (pinfunction "2_2") (pintype "passive"))
      (node (ref "C26") (pin "1") (pinfunction "1_1") (pintype "passive"))
      (node (ref "R21") (pin "1") (pinfunction "1_1") (pintype "passive"))
      (node (ref "R22") (pin "1") (pinfunction "1_1") (pintype "passive"))
      (node (ref "R23") (pin "1") (pinfunction "1_1") (pintype "passive"))
      (node (ref "U3") (pin "25") (pinfunction "AGND_25") (pintype "power_in"))
    )
    (net (code "43") (name "Net-(C16-Pad2)") (class "Default")
      (node (ref "C16") (pin "2") (pinfunction "2_2") (pintype "passive"))
      (node (ref "Q4") (pin "1") (pinfunction "SOURCE_1") (pintype "passive"))
      (node (ref "Q4") (pin "2") (pinfunction "SOURCE_2") (pintype "passive"))
      (node (ref "Q4") (pin "3") (pinfunction "SOURCE_3") (pintype "passive"))
      (node (ref "R24") (pin "2") (pinfunction "2_2") (pintype "passive"))
    )
    (net (code "44") (name "Net-(C17-Pad2)") (class "Default")
      (node (ref "C17") (pin "2") (pinfunction "2_2") (pintype "passive"))
      (node (ref "Q5") (pin "1") (pinfunction "SOURCE_1") (pintype "passive"))
      (node (ref "Q5") (pin "2") (pinfunction "SOURCE_2") (pintype "passive"))
      (node (ref "Q5") (pin "3") (pinfunction "SOURCE_3") (pintype "passive"))
      (node (ref "R25") (pin "2") (pinfunction "2_2") (pintype "passive"))
    )
    (net (code "45") (name "Net-(C18-Pad2)") (class "Default")
      (node (ref "C18") (pin "2") (pinfunction "2_2") (pintype "passive"))
      (node (ref "Q6") (pin "1") (pinfunction "SOURCE_1") (pintype "passive"))
      (node (ref "Q6") (pin "2") (pinfunction "SOURCE_2") (pintype "passive"))
      (node (ref "Q6") (pin "3") (pinfunction "SOURCE_3") (pintype "passive"))
      (node (ref "R26") (pin "2") (pinfunction "2_2") (pintype "passive"))
    )
    (net (code "46") (name "Net-(D1-PadK)") (class "Default")
      (node (ref "D1") (pin "K") (pinfunction "K_K") (pintype "passive"))
      (node (ref "R28") (pin "2") (pinfunction "2_2") (pintype "passive"))
    )
    (net (code "47") (name "Net-(U3-CPH)") (class "Default")
      (node (ref "C8") (pin "1") (pinfunction "1_1") (pintype "passive"))
      (node (ref "U3") (pin "2") (pinfunction "CPH_2") (pintype "passive"))
    )
    (net (code "48") (name "Net-(U3-CPL)") (class "Default")
      (node (ref "C8") (pin "2") (pinfunction "2_2") (pintype "passive"))
      (node (ref "U3") (pin "1") (pinfunction "CPL_1") (pintype "passive"))
    )
    (net (code "49") (name "Net-(U3-VCP)") (class "Default")
      (node (ref "C5") (pin "2") (pinfunction "2_2") (pintype "passive"))
      (node (ref "U3") (pin "5") (pinfunction "VCP_5") (pintype "power_in"))
    )
    (net (code "50") (name "Net-(U3-VGLS)") (class "Default")
      (node (ref "C25") (pin "2") (pinfunction "2_2") (pintype "passive"))
      (node (ref "U3") (pin "40") (pinfunction "VGLS_40") (pintype "power_in"))
    )
    (net (code "51") (name "VDDA_3V3") (class "Default")
      (node (ref "R29") (pin "2") (pinfunction "2_2") (pintype "passive"))
    )
    (net (code "52") (name "VDD_3V3") (class "Default")
      (node (ref "D1") (pin "A") (pinfunction "A_A") (pintype "passive"))
      (node (ref "R20") (pin "2") (pinfunction "2_2") (pintype "passive"))
      (node (ref "R27") (pin "2") (pinfunction "2_2") (pintype "passive"))
    )
    (net (code "53") (name "VDRAIN") (class "Default")
      (node (ref "C10") (pin "1") (pinfunction "1_1") (pintype "passive"))
      (node (ref "C11") (pin "1") (pinfunction "1_1") (pintype "passive"))
      (node (ref "C197") (pin "1") (pinfunction "1_1") (pintype "passive"))
      (node (ref "C198") (pin "1") (pinfunction "1_1") (pintype "passive"))
      (node (ref "C199") (pin "1") (pinfunction "1_1") (pintype "passive"))
      (node (ref "C200") (pin "1") (pinfunction "1_1") (pintype "passive"))
      (node (ref "C201") (pin "1") (pinfunction "1_1") (pintype "passive"))
      (node (ref "C202") (pin "1") (pinfunction "1_1") (pintype "passive"))
      (node (ref "C209") (pin "1") (pinfunction "1_1") (pintype "passive"))
      (node (ref "C210") (pin "1") (pinfunction "1_1") (pintype "passive"))
      (node (ref "C211") (pin "1") (pinfunction "1_1") (pintype "passive"))
      (node (ref "C5") (pin "1") (pinfunction "1_1") (pintype "passive"))
      (node (ref "C9") (pin "1") (pinfunction "1_1") (pintype "passive"))
      (node (ref "Q1") (pin "5") (pinfunction "DRAIN_5") (pintype "passive"))
      (node (ref "Q1") (pin "6") (pinfunction "DRAIN_6") (pintype "passive"))
      (node (ref "Q1") (pin "7") (pinfunction "DRAIN_7") (pintype "passive"))
      (node (ref "Q1") (pin "8") (pinfunction "DRAIN_8") (pintype "passive"))
      (node (ref "Q2") (pin "5") (pinfunction "DRAIN_5") (pintype "passive"))
      (node (ref "Q2") (pin "6") (pinfunction "DRAIN_6") (pintype "passive"))
      (node (ref "Q2") (pin "7") (pinfunction "DRAIN_7") (pintype "passive"))
      (node (ref "Q2") (pin "8") (pinfunction "DRAIN_8") (pintype "passive"))
      (node (ref "Q3") (pin "5") (pinfunction "DRAIN_5") (pintype "passive"))
      (node (ref "Q3") (pin "6") (pinfunction "DRAIN_6") (pintype "passive"))
      (node (ref "Q3") (pin "7") (pinfunction "DRAIN_7") (pintype "passive"))
      (node (ref "Q3") (pin "8") (pinfunction "DRAIN_8") (pintype "passive"))
      (node (ref "R123") (pin "1") (pinfunction "1_1") (pintype "passive"))
      (node (ref "R123") (pin "2") (pinfunction "2_2") (pintype "passive"))
      (node (ref "R124") (pin "1") (pinfunction "1_1") (pintype "passive"))
      (node (ref "R124") (pin "2") (pinfunction "2_2") (pintype "passive"))
      (node (ref "R125") (pin "1") (pinfunction "1_1") (pintype "passive"))
      (node (ref "R125") (pin "2") (pinfunction "2_2") (pintype "passive"))
      (node (ref "R126") (pin "1") (pinfunction "1_1") (pintype "passive"))
      (node (ref "R126") (pin "2") (pinfunction "2_2") (pintype "passive"))
      (node (ref "R127") (pin "1") (pinfunction "1_1") (pintype "passive"))
      (node (ref "R127") (pin "2") (pinfunction "2_2") (pintype "passive"))
      (node (ref "R128") (pin "1") (pinfunction "1_1") (pintype "passive"))
      (node (ref "R128") (pin "2") (pinfunction "2_2") (pintype "passive"))
      (node (ref "U3") (pin "4") (pinfunction "VDRAIN_4") (pintype "input"))
    )
    (net (code "54") (name "unconnected-(C*1-PadM1)") (class "Default")
      (node (ref "C*1") (pin "M1") (pinfunction "M1_M1") (pintype "passive"))
    )
    (net (code "55") (name "unconnected-(C*1-PadM2)") (class "Default")
      (node (ref "C*1") (pin "M2") (pinfunction "M2_M2") (pintype "passive"))
    )
  )
)
